# Shema.net
KiCad netlist of a schematic drawn in Altium Designer
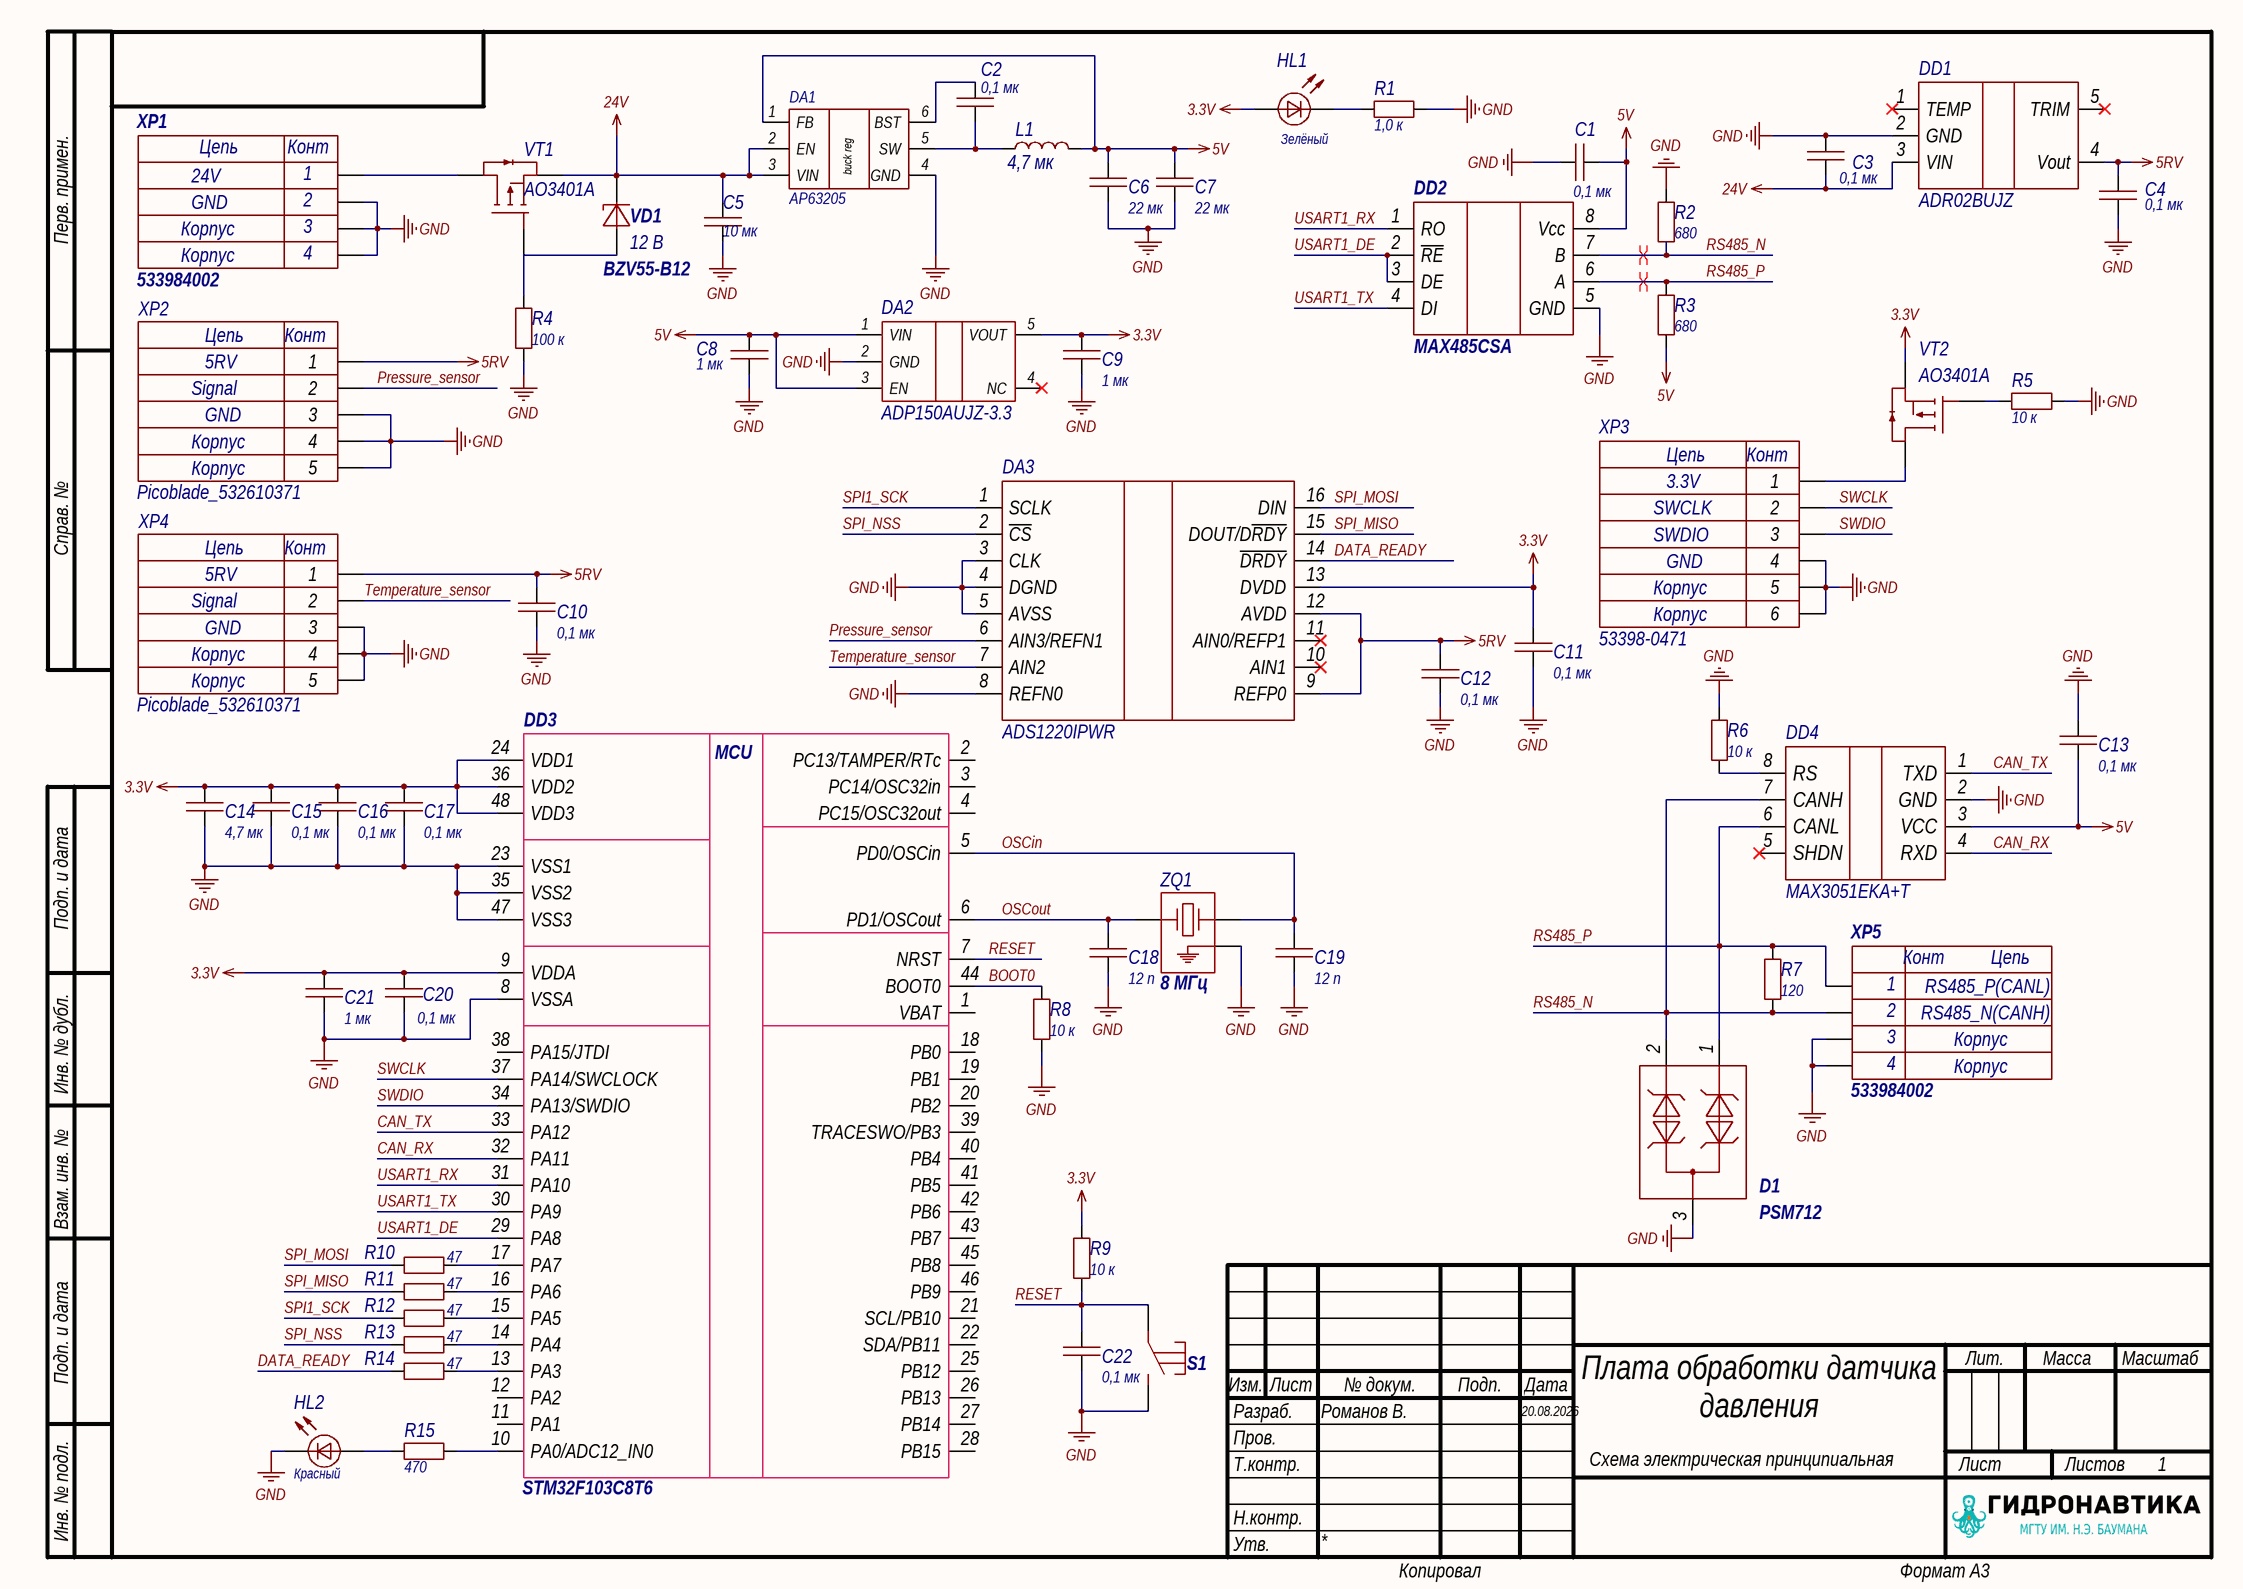
[diagram p0: Shema.SchDoc]

(export (version "E")
  (design (tool "Eeschema 10.0.6"))
  (components
    (comp (ref "C1")
      (value "0,1 мк")
      (footprint "0603C")
      (description "Конденсатор 0603C ёмкостью 0,1 мк 10%, 50 В, X7R")
      (fields (field (name "PART NUMBER") "Capacitor_0,1u_10_50V_X7R_0603C") (field (name "TOLERANCE") "10%"))
      (libsource (lib "Hydrolib") (part "Capacitor"))
    )
    (comp (ref "C2")
      (value "0,1 мк")
      (footprint "0603C")
      (description "Конденсатор 0603C ёмкостью 0,1 мк 10%, 50 В, X7R")
      (fields (field (name "PART NUMBER") "Capacitor_0,1u_10_50V_X7R_0603C") (field (name "TOLERANCE") "10%"))
      (libsource (lib "Hydrolib") (part "Capacitor"))
    )
    (comp (ref "C3")
      (value "0,1 мк")
      (footprint "0603C")
      (description "Конденсатор 0603C ёмкостью 0,1 мк 10%, 50 В, X7R")
      (fields (field (name "PART NUMBER") "Capacitor_0,1u_10_50V_X7R_0603C") (field (name "TOLERANCE") "10%"))
      (libsource (lib "Hydrolib") (part "Capacitor"))
    )
    (comp (ref "C4")
      (value "0,1 мк")
      (footprint "0603C")
      (description "Конденсатор 0603C ёмкостью 0,1 мк 10%, 50 В, X7R")
      (fields (field (name "PART NUMBER") "Capacitor_0,1u_10_50V_X7R_0603C") (field (name "TOLERANCE") "10%"))
      (libsource (lib "Hydrolib") (part "Capacitor"))
    )
    (comp (ref "C5")
      (value "10 мк")
      (footprint "1210C")
      (description "Конденсатор 1210C ёмкостью 10 мк 10%, 35 В, X7R")
      (fields (field (name "PART NUMBER") "Capacitor_10u_10_35V_X7R_1210C") (field (name "TOLERANCE") "10%"))
      (libsource (lib "Hydrolib") (part "Capacitor"))
    )
    (comp (ref "C6")
      (value "22 мк")
      (footprint "1210C")
      (description "Конденсатор 1210C ёмкостью 22 мк 10%, 25 В, X7R")
      (fields (field (name "PART NUMBER") "Capacitor_22u_10_25V_X7R_1210C") (field (name "TOLERANCE") "10%"))
      (libsource (lib "Hydrolib") (part "Capacitor"))
    )
    (comp (ref "C7")
      (value "22 мк")
      (footprint "1210C")
      (description "Конденсатор 1210C ёмкостью 22 мк 10%, 25 В, X7R")
      (fields (field (name "PART NUMBER") "Capacitor_22u_10_25V_X7R_1210C") (field (name "TOLERANCE") "10%"))
      (libsource (lib "Hydrolib") (part "Capacitor"))
    )
    (comp (ref "C8")
      (value "1 мк")
      (footprint "0603C")
      (description "Конденсатор 0603C ёмкостью 1 мк 10%, 25 В, X7R")
      (fields (field (name "PART NUMBER") "Capacitor_1u_10_25V_X7R_0603C") (field (name "TOLERANCE") "10%"))
      (libsource (lib "Hydrolib") (part "Capacitor"))
    )
    (comp (ref "C9")
      (value "1 мк")
      (footprint "0603C")
      (description "Конденсатор 0603C ёмкостью 1 мк 10%, 25 В, X7R")
      (fields (field (name "PART NUMBER") "Capacitor_1u_10_25V_X7R_0603C") (field (name "TOLERANCE") "10%"))
      (libsource (lib "Hydrolib") (part "Capacitor"))
    )
    (comp (ref "C10")
      (value "0,1 мк")
      (footprint "0603C")
      (description "Конденсатор 0603C ёмкостью 0,1 мк 10%, 50 В, X7R")
      (fields (field (name "PART NUMBER") "Capacitor_0,1u_10_50V_X7R_0603C") (field (name "TOLERANCE") "10%"))
      (libsource (lib "Hydrolib") (part "Capacitor"))
    )
    (comp (ref "C11")
      (value "0,1 мк")
      (footprint "0603C")
      (description "Конденсатор 0603C ёмкостью 0,1 мк 10%, 50 В, X7R")
      (fields (field (name "PART NUMBER") "Capacitor_0,1u_10_50V_X7R_0603C") (field (name "TOLERANCE") "10%"))
      (libsource (lib "Hydrolib") (part "Capacitor"))
    )
    (comp (ref "C12")
      (value "0,1 мк")
      (footprint "0603C")
      (description "Конденсатор 0603C ёмкостью 0,1 мк 10%, 50 В, X7R")
      (fields (field (name "PART NUMBER") "Capacitor_0,1u_10_50V_X7R_0603C") (field (name "TOLERANCE") "10%"))
      (libsource (lib "Hydrolib") (part "Capacitor"))
    )
    (comp (ref "C13")
      (value "0,1 мк")
      (footprint "0603C")
      (description "Конденсатор 0603C ёмкостью 0,1 мк 10%, 50 В, X7R")
      (fields (field (name "PART NUMBER") "Capacitor_0,1u_10_50V_X7R_0603C") (field (name "TOLERANCE") "10%"))
      (libsource (lib "Hydrolib") (part "Capacitor"))
    )
    (comp (ref "C14")
      (value "4,7 мк")
      (footprint "1206C")
      (description "Конденсатор 1206C ёмкостью 4,7 мк 10%, 50 В, X7R")
      (fields (field (name "PART NUMBER") "Capacitor_4,7u_10_50V_X7R_1206C") (field (name "TOLERANCE") "10%"))
      (libsource (lib "Hydrolib") (part "Capacitor"))
    )
    (comp (ref "C15")
      (value "0,1 мк")
      (footprint "0603C")
      (description "Конденсатор 0603C ёмкостью 0,1 мк 10%, 50 В, X7R")
      (fields (field (name "PART NUMBER") "Capacitor_0,1u_10_50V_X7R_0603C") (field (name "TOLERANCE") "10%"))
      (libsource (lib "Hydrolib") (part "Capacitor"))
    )
    (comp (ref "C16")
      (value "0,1 мк")
      (footprint "0603C")
      (description "Конденсатор 0603C ёмкостью 0,1 мк 10%, 50 В, X7R")
      (fields (field (name "PART NUMBER") "Capacitor_0,1u_10_50V_X7R_0603C") (field (name "TOLERANCE") "10%"))
      (libsource (lib "Hydrolib") (part "Capacitor"))
    )
    (comp (ref "C17")
      (value "0,1 мк")
      (footprint "0603C")
      (description "Конденсатор 0603C ёмкостью 0,1 мк 10%, 50 В, X7R")
      (fields (field (name "PART NUMBER") "Capacitor_0,1u_10_50V_X7R_0603C") (field (name "TOLERANCE") "10%"))
      (libsource (lib "Hydrolib") (part "Capacitor"))
    )
    (comp (ref "C18")
      (value "12 п")
      (footprint "0603C")
      (description "Конденсатор 0603C ёмкостью 12 п 5%, 50 В, NP0")
      (fields
        (field (name "PART NUMBER") "Capacitor_12p_5_50V_NP0_0603C")
        (field (name "TOLERANCE") "5%")
        (field (name "АВТОР") "glebmih")
      )
      (libsource (lib "Hydrolib") (part "Capacitor"))
    )
    (comp (ref "C19")
      (value "12 п")
      (footprint "0603C")
      (description "Конденсатор 0603C ёмкостью 12 п 5%, 50 В, NP0")
      (fields
        (field (name "PART NUMBER") "Capacitor_12p_5_50V_NP0_0603C")
        (field (name "TOLERANCE") "5%")
        (field (name "АВТОР") "glebmih")
      )
      (libsource (lib "Hydrolib") (part "Capacitor"))
    )
    (comp (ref "C20")
      (value "0,1 мк")
      (footprint "0603C")
      (description "Конденсатор 0603C ёмкостью 0,1 мк 10%, 50 В, X7R")
      (fields (field (name "PART NUMBER") "Capacitor_0,1u_10_50V_X7R_0603C") (field (name "TOLERANCE") "10%"))
      (libsource (lib "Hydrolib") (part "Capacitor"))
    )
    (comp (ref "C21")
      (value "1 мк")
      (footprint "0603C")
      (description "Конденсатор 0603C ёмкостью 1 мк 10%, 25 В, X7R")
      (fields (field (name "PART NUMBER") "Capacitor_1u_10_25V_X7R_0603C") (field (name "TOLERANCE") "10%"))
      (libsource (lib "Hydrolib") (part "Capacitor"))
    )
    (comp (ref "C22")
      (value "0,1 мк")
      (footprint "0603C")
      (description "Конденсатор 0603C ёмкостью 0,1 мк 10%, 50 В, X7R")
      (fields (field (name "PART NUMBER") "Capacitor_0,1u_10_50V_X7R_0603C") (field (name "TOLERANCE") "10%"))
      (libsource (lib "Hydrolib") (part "Capacitor"))
    )
    (comp (ref "D1")
      (value "PSM712")
      (footprint "SOT23-3")
      (description "Защитный диод для линии RS-485")
      (libsource (lib "Hydrolib") (part "TVS_2_2dir"))
    )
    (comp (ref "DA1")
      (value "AP63205")
      (footprint "TSOT26")
      (description "DC-DC понижающий преобразователь, Vin: 3.8 - 40 В; 5 В; 2 А")
      (fields (field (name "АВТОР") "glebmih"))
      (libsource (lib "Hydrolib") (part "AP63205"))
    )
    (comp (ref "DA2")
      (value "ADP150AUJZ-3.3")
      (footprint "SOT23-5")
      (description "Стабилизатор напряжения 3.3В 150мА")
      (fields (field (name "АВТОР") "glebmih"))
      (libsource (lib "Hydrolib") (part "ADP150AUJZ-3.3"))
    )
    (comp (ref "DA3")
      (value "ADS1220IPWR")
      (footprint "TSSOP-16")
      (description "24-Бит Sigma-Delta аналого-цифровой преобразователь")
      (fields (field (name "АВТОР") "Vouka06"))
      (libsource (lib "Hydrolib") (part "ADS1220IPWR"))
    )
    (comp (ref "DD1")
      (value "ADR02BUJZ")
      (footprint "SOT23-5")
      (description "Источник опорного напряжения, 5В")
      (fields (field (name "АВТОР") "Vouka05"))
      (libsource (lib "Hydrolib") (part "ADR02BUJZ"))
    )
    (comp (ref "DD2")
      (value "MAX485CSA")
      (footprint "SOIC-8")
      (description "RS-485 приёмопередатчик")
      (libsource (lib "Hydrolib") (part "MAX485CSA"))
    )
    (comp (ref "DD3")
      (value "STM32F103C8T6")
      (footprint "LQFP48")
      (description "Микроконтроллер")
      (fields (field (name "MANUFACTURER") "ST Microelectronics") (field (name "VALUE1") "MCU"))
      (libsource (lib "Hydrolib") (part "STM32F103C8T6"))
    )
    (comp (ref "DD4")
      (value "MAX3051EKA+T")
      (footprint "SOT-23-8")
      (description "CAN трансивер 1Mbps +3.3В")
      (fields (field (name "АВТОР") "Vouka06"))
      (libsource (lib "Hydrolib") (part "MAX3051EKA+T"))
    )
    (comp (ref "HL1")
      (value "Зелёный")
      (footprint "0805D")
      (description "Светодиод")
      (fields (field (name "PART NUMBER") "LED"))
      (libsource (lib "Hydrolib") (part "LED"))
    )
    (comp (ref "HL2")
      (value "Красный")
      (footprint "0805D")
      (description "Светодиод")
      (fields (field (name "PART NUMBER") "LED"))
      (libsource (lib "Hydrolib") (part "LED"))
    )
    (comp (ref "L1")
      (value "4,7 мк")
      (footprint "IHLP-2525")
      (description "ЧИП-индуктивность экранированная 4,7мкГн ±20% 5,5A 40мОм 2525")
      (fields (field (name "PART NUMBER") "IHLP2525CZER4R7M01"))
      (libsource (lib "Hydrolib") (part "Inductance"))
    )
    (comp (ref "R1")
      (value "1,0 к")
      (footprint "0603R")
      (description "Резистор номиналом 1,0 кОм 1%")
      (fields (field (name "PART NUMBER") "Resistor_1.0k_1_0603") (field (name "TOLERANCE") "1%"))
      (libsource (lib "") (part "Resistor_2"))
    )
    (comp (ref "R2")
      (value "680")
      (footprint "0603R")
      (description "Резистор номиналом 680 Ом 1%")
      (fields (field (name "PART NUMBER") "Resistor_680_1_0603") (field (name "TOLERANCE") "1%"))
      (libsource (lib "") (part "Resistor_1"))
    )
    (comp (ref "R3")
      (value "680")
      (footprint "0603R")
      (description "Резистор номиналом 680 Ом 1%")
      (fields (field (name "PART NUMBER") "Resistor_680_1_0603") (field (name "TOLERANCE") "1%"))
      (libsource (lib "") (part "Resistor_1"))
    )
    (comp (ref "R4")
      (value "100 к")
      (footprint "0603R")
      (description "Резистор номиналом 100 кОм 1%")
      (fields (field (name "PART NUMBER") "Resistor_100k_1_0603") (field (name "TOLERANCE") "1%"))
      (libsource (lib "") (part "Resistor_1"))
    )
    (comp (ref "R5")
      (value "10 к")
      (footprint "0603R")
      (description "Резистор номиналом 10 кОм 1%")
      (fields (field (name "PART NUMBER") "Resistor_10k_1_0603") (field (name "TOLERANCE") "1%"))
      (libsource (lib "") (part "Resistor_2"))
    )
    (comp (ref "R6")
      (value "10 к")
      (footprint "0603R")
      (description "Резистор номиналом 10 кОм 1%")
      (fields (field (name "PART NUMBER") "Resistor_10k_1_0603") (field (name "TOLERANCE") "1%"))
      (libsource (lib "") (part "Resistor_2"))
    )
    (comp (ref "R7")
      (value "120")
      (footprint "0603R")
      (description "Резистор номиналом 120 Ом 1%")
      (fields (field (name "PART NUMBER") "Resistor_120_1_0603") (field (name "TOLERANCE") "1%"))
      (libsource (lib "") (part "Resistor_1"))
    )
    (comp (ref "R8")
      (value "10 к")
      (footprint "0603R")
      (description "Резистор номиналом 10 кОм 1%")
      (fields (field (name "PART NUMBER") "Resistor_10k_1_0603") (field (name "TOLERANCE") "1%"))
      (libsource (lib "Hydrolib") (part "Resistor"))
    )
    (comp (ref "R9")
      (value "10 к")
      (footprint "0603R")
      (description "Резистор номиналом 10 кОм 1%")
      (fields (field (name "PART NUMBER") "Resistor_10k_1_0603") (field (name "TOLERANCE") "1%"))
      (libsource (lib "Hydrolib") (part "Resistor"))
    )
    (comp (ref "R10")
      (value "47")
      (footprint "0603R")
      (description "Резистор номиналом 47 Ом 1%")
      (fields (field (name "PART NUMBER") "Resistor_47_1_0603") (field (name "TOLERANCE") "1%"))
      (libsource (lib "") (part "Resistor_2"))
    )
    (comp (ref "R11")
      (value "47")
      (footprint "0603R")
      (description "Резистор номиналом 47 Ом 1%")
      (fields (field (name "PART NUMBER") "Resistor_47_1_0603") (field (name "TOLERANCE") "1%"))
      (libsource (lib "") (part "Resistor_2"))
    )
    (comp (ref "R12")
      (value "47")
      (footprint "0603R")
      (description "Резистор номиналом 47 Ом 1%")
      (fields (field (name "PART NUMBER") "Resistor_47_1_0603") (field (name "TOLERANCE") "1%"))
      (libsource (lib "") (part "Resistor_2"))
    )
    (comp (ref "R13")
      (value "47")
      (footprint "0603R")
      (description "Резистор номиналом 47 Ом 1%")
      (fields (field (name "PART NUMBER") "Resistor_47_1_0603") (field (name "TOLERANCE") "1%"))
      (libsource (lib "") (part "Resistor_2"))
    )
    (comp (ref "R14")
      (value "47")
      (footprint "0603R")
      (description "Резистор номиналом 47 Ом 1%")
      (fields (field (name "PART NUMBER") "Resistor_47_1_0603") (field (name "TOLERANCE") "1%"))
      (libsource (lib "") (part "Resistor_2"))
    )
    (comp (ref "R15")
      (value "470")
      (footprint "0603R")
      (description "Резистор номиналом 470 Ом 1%")
      (fields (field (name "PART NUMBER") "Resistor_470_1_0603") (field (name "TOLERANCE") "1%"))
      (libsource (lib "") (part "Resistor_2"))
    )
    (comp (ref "S1")
      (value "Tact_button")
      (footprint "Button_SMD_10mm")
      (description "Тактовая кнопка")
      (libsource (lib "Hydrolib") (part "Tact_button"))
    )
    (comp (ref "VD1")
      (value "BZV55-B12")
      (footprint "mini_MELF_3.5mm")
      (description "Стабилитрон 12В, 5%, 0.5Вт")
      (fields (field (name "ALTIUM_VALUE") "12 В") (field (name "АВТОР") "rreali"))
      (libsource (lib "Hydrolib") (part "Zener"))
    )
    (comp (ref "VT1")
      (value "AO3401A")
      (footprint "SOT23-3")
      (description "P-канальный MOSFET")
      (libsource (lib "Hydrolib") (part "MOSFET P-channel 2"))
    )
    (comp (ref "VT2")
      (value "AO3401A")
      (footprint "SOT23-3")
      (description "P-канальный MOSFET")
      (libsource (lib "Hydrolib") (part "MOSFET P-channel 2"))
    )
    (comp (ref "XP1")
      (value "533984002")
      (footprint "Picoblade_533984002")
      (description "2pin, 1.25mm, вилка, PicoBlade, на плату, SMT")
      (fields
        (field (name "VALUE3") "Корпус")
        (field (name "VALUE2") "GND")
        (field (name "VALUE4") "Корпус")
        (field (name "VALUE1") "24V")
        (field (name "PART NUMBER") "Picoblade_533984002")
        (field (name "АВТОР") "rreali")
      )
      (libsource (lib "Hydrolib") (part "Conn_2pin_2shield"))
    )
    (comp (ref "XP2")
      (value "Picoblade_532610371")
      (footprint "CONN_532610001-SD_03_MOL")
      (description "Picoblade 3-pin разъем")
      (fields
        (field (name "VALUE5") "Корпус")
        (field (name "VALUE4") "Корпус")
        (field (name "VALUE3") "GND")
        (field (name "VALUE2") "Signal")
        (field (name "VALUE1") "5RV")
        (field (name "АВТОР") "Vouka06")
      )
      (libsource (lib "Hydrolib") (part "Picoblade_532610371"))
    )
    (comp (ref "XP3")
      (value "53398-0471")
      (footprint "53398-0471")
      (description "Разъем PicoBlade 1.25 мм, 4pin")
      (fields
        (field (name "VALUE6") "Корпус")
        (field (name "VALUE5") "Корпус")
        (field (name "VALUE4") "GND")
        (field (name "VALUE3") "SWDIO")
        (field (name "VALUE2") "SWCLK")
        (field (name "VALUE1") "3.3V")
        (field (name "PART NUMBER") "PicoBlade_53398-0471")
        (field (name "АВТОР") "Vouka06")
      )
      (libsource (lib "Hydrolib") (part "PicoBlade_53398-0471"))
    )
    (comp (ref "XP4")
      (value "Picoblade_532610371")
      (footprint "CONN_532610001-SD_03_MOL")
      (description "Picoblade 3-pin разъем")
      (fields
        (field (name "VALUE5") "Корпус")
        (field (name "VALUE4") "Корпус")
        (field (name "VALUE3") "GND")
        (field (name "VALUE2") "Signal")
        (field (name "VALUE1") "5RV")
        (field (name "АВТОР") "Vouka06")
      )
      (libsource (lib "Hydrolib") (part "Picoblade_532610371"))
    )
    (comp (ref "XP5")
      (value "533984002")
      (footprint "Picoblade_533984002")
      (description "2pin, 1.25mm, вилка, PicoBlade, на плату, SMT")
      (fields
        (field (name "VALUE3") "Корпус")
        (field (name "VALUE2") "RS485_N(CANH)")
        (field (name "VALUE4") "Корпус")
        (field (name "VALUE1") "RS485_P(CANL)")
        (field (name "PART NUMBER") "Picoblade_533984002")
        (field (name "АВТОР") "rreali")
      )
      (libsource (lib "Hydrolib") (part "Conn_2pin_2shield"))
    )
    (comp (ref "ZQ1")
      (value "8 МГц")
      (footprint "QSMD3.2x2.5")
      (description "Кварцевый резонатор с входом земли")
      (fields (field (name "PART NUMBER") "XTAL_GND"))
      (libsource (lib "Hydrolib") (part "XTAL_GND"))
    )
  )
  (nets
    (net (code "1") (name "/BOOT0") (class "Default")
      (node (ref "DD3") (pin "44") (pinfunction "BOOT0_44") (pintype "passive"))
      (node (ref "R8") (pin "1") (pinfunction "1_1") (pintype "passive"))
    )
    (net (code "2") (name "/CAN_RX") (class "Default")
      (node (ref "DD3") (pin "32") (pinfunction "PA11_32") (pintype "passive"))
      (node (ref "DD4") (pin "4") (pinfunction "RXD_4") (pintype "passive"))
    )
    (net (code "3") (name "/CAN_TX") (class "Default")
      (node (ref "DD3") (pin "33") (pinfunction "PA12_33") (pintype "passive"))
      (node (ref "DD4") (pin "1") (pinfunction "TXD_1") (pintype "passive"))
    )
    (net (code "4") (name "/DATA_READY") (class "Default")
      (node (ref "DA3") (pin "14") (pinfunction "~{DRDY}_14") (pintype "passive"))
      (node (ref "R14") (pin "1") (pinfunction "1_1") (pintype "passive"))
    )
    (net (code "5") (name "/OSCin") (class "Default")
      (node (ref "C19") (pin "2") (pinfunction "2_2") (pintype "passive"))
      (node (ref "DD3") (pin "5") (pinfunction "PD0/OSCin_5") (pintype "passive"))
      (node (ref "ZQ1") (pin "2") (pinfunction "2_2") (pintype "passive"))
    )
    (net (code "6") (name "/OSCout") (class "Default")
      (node (ref "C18") (pin "2") (pinfunction "2_2") (pintype "passive"))
      (node (ref "DD3") (pin "6") (pinfunction "PD1/OSCout_6") (pintype "passive"))
      (node (ref "ZQ1") (pin "1") (pinfunction "1_1") (pintype "passive"))
    )
    (net (code "7") (name "/Pressure_sensor") (class "Default")
      (node (ref "DA3") (pin "6") (pinfunction "AIN3/REFN1_6") (pintype "passive"))
      (node (ref "XP2") (pin "2") (pinfunction "2_2") (pintype "passive"))
    )
    (net (code "8") (name "/RESET") (class "Default")
      (node (ref "C22") (pin "1") (pinfunction "1_1") (pintype "passive"))
      (node (ref "DD3") (pin "7") (pinfunction "NRST_7") (pintype "passive"))
      (node (ref "R9") (pin "2") (pinfunction "2_2") (pintype "passive"))
      (node (ref "S1") (pin "1") (pinfunction "1_1") (pintype "passive"))
    )
    (net (code "9") (name "/RS485_N") (class "Default")
      (node (ref "D1") (pin "2") (pinfunction "15_2") (pintype "passive"))
      (node (ref "DD2") (pin "7") (pinfunction "B_7") (pintype "passive"))
      (node (ref "DD4") (pin "7") (pinfunction "CANH_7") (pintype "passive"))
      (node (ref "R2") (pin "1") (pinfunction "1_1") (pintype "passive"))
      (node (ref "R7") (pin "1") (pinfunction "1_1") (pintype "passive"))
      (node (ref "XP5") (pin "2") (pinfunction "2_2") (pintype "passive"))
    )
    (net (code "10") (name "/RS485_P") (class "Default")
      (node (ref "D1") (pin "1") (pinfunction "14_1") (pintype "passive"))
      (node (ref "DD2") (pin "6") (pinfunction "A_6") (pintype "passive"))
      (node (ref "DD4") (pin "6") (pinfunction "CANL_6") (pintype "passive"))
      (node (ref "R3") (pin "2") (pinfunction "2_2") (pintype "passive"))
      (node (ref "R7") (pin "2") (pinfunction "2_2") (pintype "passive"))
      (node (ref "XP5") (pin "1") (pinfunction "1_1") (pintype "passive"))
    )
    (net (code "11") (name "/SPI1_SCK") (class "Default")
      (node (ref "DA3") (pin "1") (pinfunction "SCLK_1") (pintype "passive"))
      (node (ref "R12") (pin "1") (pinfunction "1_1") (pintype "passive"))
    )
    (net (code "12") (name "/SPI_MISO") (class "Default")
      (node (ref "DA3") (pin "15") (pinfunction "DOUT/D~{RDY}_15") (pintype "passive"))
      (node (ref "R11") (pin "1") (pinfunction "1_1") (pintype "passive"))
    )
    (net (code "13") (name "/SPI_MOSI") (class "Default")
      (node (ref "DA3") (pin "16") (pinfunction "DIN_16") (pintype "passive"))
      (node (ref "R10") (pin "1") (pinfunction "1_1") (pintype "passive"))
    )
    (net (code "14") (name "/SPI_NSS") (class "Default")
      (node (ref "DA3") (pin "2") (pinfunction "~{CS}_2") (pintype "passive"))
      (node (ref "R13") (pin "1") (pinfunction "1_1") (pintype "passive"))
    )
    (net (code "15") (name "/SWCLK") (class "Default")
      (node (ref "DD3") (pin "37") (pinfunction "PA14/SWCLOCK_37") (pintype "passive"))
      (node (ref "XP3") (pin "2") (pinfunction "2_2") (pintype "passive"))
    )
    (net (code "16") (name "/SWDIO") (class "Default")
      (node (ref "DD3") (pin "34") (pinfunction "PA13/SWDIO_34") (pintype "passive"))
      (node (ref "XP3") (pin "3") (pinfunction "3_3") (pintype "passive"))
    )
    (net (code "17") (name "/Temperature_sensor") (class "Default")
      (node (ref "DA3") (pin "7") (pinfunction "AIN2_7") (pintype "passive"))
      (node (ref "XP4") (pin "2") (pinfunction "2_2") (pintype "passive"))
    )
    (net (code "18") (name "/USART1_DE") (class "Default")
      (node (ref "DD2") (pin "2") (pinfunction "RE_2") (pintype "passive"))
      (node (ref "DD2") (pin "3") (pinfunction "DE_3") (pintype "passive"))
      (node (ref "DD3") (pin "29") (pinfunction "PA8_29") (pintype "passive"))
    )
    (net (code "19") (name "/USART1_RX") (class "Default")
      (node (ref "DD2") (pin "1") (pinfunction "RO_1") (pintype "passive"))
      (node (ref "DD3") (pin "31") (pinfunction "PA10_31") (pintype "passive"))
    )
    (net (code "20") (name "/USART1_TX") (class "Default")
      (node (ref "DD2") (pin "4") (pinfunction "DI_4") (pintype "passive"))
      (node (ref "DD3") (pin "30") (pinfunction "PA9_30") (pintype "passive"))
    )
    (net (code "21") (name "3.3V") (class "Default")
      (node (ref "C11") (pin "2") (pinfunction "2_2") (pintype "passive"))
      (node (ref "C14") (pin "2") (pinfunction "2_2") (pintype "passive"))
      (node (ref "C15") (pin "2") (pinfunction "2_2") (pintype "passive"))
      (node (ref "C16") (pin "2") (pinfunction "2_2") (pintype "passive"))
      (node (ref "C17") (pin "2") (pinfunction "2_2") (pintype "passive"))
      (node (ref "C20") (pin "2") (pinfunction "2_2") (pintype "passive"))
      (node (ref "C21") (pin "2") (pinfunction "2_2") (pintype "passive"))
      (node (ref "C9") (pin "2") (pinfunction "2_2") (pintype "passive"))
      (node (ref "DA2") (pin "5") (pinfunction "VOUT_5") (pintype "passive"))
      (node (ref "DA3") (pin "13") (pinfunction "DVDD_13") (pintype "passive"))
      (node (ref "DD3") (pin "24") (pinfunction "VDD1_24") (pintype "passive"))
      (node (ref "DD3") (pin "36") (pinfunction "VDD2_36") (pintype "passive"))
      (node (ref "DD3") (pin "48") (pinfunction "VDD3_48") (pintype "passive"))
      (node (ref "DD3") (pin "9") (pinfunction "VDDA_9") (pintype "passive"))
      (node (ref "HL1") (pin "1") (pinfunction "1_1") (pintype "passive"))
      (node (ref "R9") (pin "1") (pinfunction "1_1") (pintype "passive"))
      (node (ref "VT2") (pin "2") (pinfunction "2_2") (pintype "passive"))
    )
    (net (code "22") (name "5RV") (class "Default")
      (node (ref "C10") (pin "2") (pinfunction "2_2") (pintype "passive"))
      (node (ref "C12") (pin "2") (pinfunction "2_2") (pintype "passive"))
      (node (ref "C4") (pin "2") (pinfunction "2_2") (pintype "passive"))
      (node (ref "DA3") (pin "12") (pinfunction "AVDD_12") (pintype "passive"))
      (node (ref "DA3") (pin "9") (pinfunction "REFP0_9") (pintype "passive"))
      (node (ref "DD1") (pin "4") (pinfunction "Vout_4") (pintype "passive"))
      (node (ref "XP2") (pin "1") (pinfunction "1_1") (pintype "passive"))
      (node (ref "XP4") (pin "1") (pinfunction "1_1") (pintype "passive"))
    )
    (net (code "23") (name "5V") (class "Default")
      (node (ref "C1") (pin "2") (pinfunction "2_2") (pintype "passive"))
      (node (ref "C13") (pin "2") (pinfunction "2_2") (pintype "passive"))
      (node (ref "C6") (pin "2") (pinfunction "2_2") (pintype "passive"))
      (node (ref "C7") (pin "2") (pinfunction "2_2") (pintype "passive"))
      (node (ref "C8") (pin "2") (pinfunction "2_2") (pintype "passive"))
      (node (ref "DA1") (pin "1") (pinfunction "FB_1") (pintype "passive"))
      (node (ref "DA2") (pin "1") (pinfunction "VIN_1") (pintype "passive"))
      (node (ref "DA2") (pin "3") (pinfunction "EN_3") (pintype "passive"))
      (node (ref "DD2") (pin "8") (pinfunction "Vcc_8") (pintype "passive"))
      (node (ref "DD4") (pin "3") (pinfunction "VCC_3") (pintype "passive"))
      (node (ref "L1") (pin "2") (pinfunction "2_2") (pintype "passive"))
      (node (ref "R3") (pin "1") (pinfunction "1_1") (pintype "passive"))
    )
    (net (code "24") (name "24V") (class "Default")
      (node (ref "C3") (pin "1") (pinfunction "1_1") (pintype "passive"))
      (node (ref "C5") (pin "2") (pinfunction "2_2") (pintype "passive"))
      (node (ref "DA1") (pin "2") (pinfunction "EN_2") (pintype "passive"))
      (node (ref "DA1") (pin "3") (pinfunction "VIN_3") (pintype "passive"))
      (node (ref "DD1") (pin "3") (pinfunction "VIN_3") (pintype "passive"))
      (node (ref "VD1") (pin "2") (pinfunction "2_2") (pintype "passive"))
      (node (ref "VT1") (pin "2") (pinfunction "2_2") (pintype "passive"))
    )
    (net (code "25") (name "GND") (class "Default")
      (node (ref "C1") (pin "1") (pinfunction "1_1") (pintype "passive"))
      (node (ref "C10") (pin "1") (pinfunction "1_1") (pintype "passive"))
      (node (ref "C11") (pin "1") (pinfunction "1_1") (pintype "passive"))
      (node (ref "C12") (pin "1") (pinfunction "1_1") (pintype "passive"))
      (node (ref "C13") (pin "1") (pinfunction "1_1") (pintype "passive"))
      (node (ref "C14") (pin "1") (pinfunction "1_1") (pintype "passive"))
      (node (ref "C15") (pin "1") (pinfunction "1_1") (pintype "passive"))
      (node (ref "C16") (pin "1") (pinfunction "1_1") (pintype "passive"))
      (node (ref "C17") (pin "1") (pinfunction "1_1") (pintype "passive"))
      (node (ref "C18") (pin "1") (pinfunction "1_1") (pintype "passive"))
      (node (ref "C19") (pin "1") (pinfunction "1_1") (pintype "passive"))
      (node (ref "C20") (pin "1") (pinfunction "1_1") (pintype "passive"))
      (node (ref "C21") (pin "1") (pinfunction "1_1") (pintype "passive"))
      (node (ref "C22") (pin "2") (pinfunction "2_2") (pintype "passive"))
      (node (ref "C3") (pin "2") (pinfunction "2_2") (pintype "passive"))
      (node (ref "C4") (pin "1") (pinfunction "1_1") (pintype "passive"))
      (node (ref "C5") (pin "1") (pinfunction "1_1") (pintype "passive"))
      (node (ref "C6") (pin "1") (pinfunction "1_1") (pintype "passive"))
      (node (ref "C7") (pin "1") (pinfunction "1_1") (pintype "passive"))
      (node (ref "C8") (pin "1") (pinfunction "1_1") (pintype "passive"))
      (node (ref "C9") (pin "1") (pinfunction "1_1") (pintype "passive"))
      (node (ref "D1") (pin "3") (pinfunction "16_3") (pintype "passive"))
      (node (ref "DA1") (pin "4") (pinfunction "GND_4") (pintype "passive"))
      (node (ref "DA2") (pin "2") (pinfunction "GND_2") (pintype "passive"))
      (node (ref "DA3") (pin "3") (pinfunction "CLK_3") (pintype "passive"))
      (node (ref "DA3") (pin "4") (pinfunction "DGND_4") (pintype "passive"))
      (node (ref "DA3") (pin "5") (pinfunction "AVSS_5") (pintype "passive"))
      (node (ref "DA3") (pin "8") (pinfunction "REFN0_8") (pintype "passive"))
      (node (ref "DD1") (pin "2") (pinfunction "GND_2") (pintype "passive"))
      (node (ref "DD2") (pin "5") (pinfunction "GND_5") (pintype "passive"))
      (node (ref "DD3") (pin "23") (pinfunction "VSS1_23") (pintype "passive"))
      (node (ref "DD3") (pin "35") (pinfunction "VSS2_35") (pintype "passive"))
      (node (ref "DD3") (pin "47") (pinfunction "VSS3_47") (pintype "passive"))
      (node (ref "DD3") (pin "8") (pinfunction "VSSA_8") (pintype "passive"))
      (node (ref "DD4") (pin "2") (pinfunction "GND_2") (pintype "passive"))
      (node (ref "HL2") (pin "2") (pinfunction "2_2") (pintype "passive"))
      (node (ref "R1") (pin "2") (pinfunction "2_2") (pintype "passive"))
      (node (ref "R2") (pin "2") (pinfunction "2_2") (pintype "passive"))
      (node (ref "R4") (pin "1") (pinfunction "1_1") (pintype "passive"))
      (node (ref "R5") (pin "2") (pinfunction "2_2") (pintype "passive"))
      (node (ref "R6") (pin "2") (pinfunction "2_2") (pintype "passive"))
      (node (ref "R8") (pin "2") (pinfunction "2_2") (pintype "passive"))
      (node (ref "S1") (pin "2") (pinfunction "2_2") (pintype "passive"))
      (node (ref "XP1") (pin "2") (pinfunction "2_2") (pintype "passive"))
      (node (ref "XP1") (pin "3") (pinfunction "3_3") (pintype "passive"))
      (node (ref "XP1") (pin "4") (pinfunction "4_4") (pintype "passive"))
      (node (ref "XP2") (pin "3") (pinfunction "3_3") (pintype "passive"))
      (node (ref "XP2") (pin "4") (pinfunction "4_4") (pintype "passive"))
      (node (ref "XP2") (pin "5") (pinfunction "5_5") (pintype "passive"))
      (node (ref "XP3") (pin "4") (pinfunction "4_4") (pintype "passive"))
      (node (ref "XP3") (pin "5") (pinfunction "5_5") (pintype "passive"))
      (node (ref "XP3") (pin "6") (pinfunction "6_6") (pintype "passive"))
      (node (ref "XP4") (pin "3") (pinfunction "3_3") (pintype "passive"))
      (node (ref "XP4") (pin "4") (pinfunction "4_4") (pintype "passive"))
      (node (ref "XP4") (pin "5") (pinfunction "5_5") (pintype "passive"))
      (node (ref "XP5") (pin "3") (pinfunction "3_3") (pintype "passive"))
      (node (ref "XP5") (pin "4") (pinfunction "4_4") (pintype "passive"))
      (node (ref "ZQ1") (pin "3") (pinfunction "3_3") (pintype "passive"))
    )
    (net (code "26") (name "Net-(DA1-BST)") (class "Default")
      (node (ref "C2") (pin "2") (pinfunction "2_2") (pintype "passive"))
      (node (ref "DA1") (pin "6") (pinfunction "BST_6") (pintype "passive"))
    )
    (net (code "27") (name "Net-(DA1-SW)") (class "Default")
      (node (ref "C2") (pin "1") (pinfunction "1_1") (pintype "passive"))
      (node (ref "DA1") (pin "5") (pinfunction "SW_5") (pintype "passive"))
      (node (ref "L1") (pin "1") (pinfunction "1_1") (pintype "passive"))
    )
    (net (code "28") (name "Net-(DD3-PA0{slash}ADC12_IN0)") (class "Default")
      (node (ref "DD3") (pin "10") (pinfunction "PA0/ADC12_IN0_10") (pintype "passive"))
      (node (ref "R15") (pin "2") (pinfunction "2_2") (pintype "passive"))
    )
    (net (code "29") (name "Net-(DD3-PA3)") (class "Default")
      (node (ref "DD3") (pin "13") (pinfunction "PA3_13") (pintype "passive"))
      (node (ref "R14") (pin "2") (pinfunction "2_2") (pintype "passive"))
    )
    (net (code "30") (name "Net-(DD3-PA4)") (class "Default")
      (node (ref "DD3") (pin "14") (pinfunction "PA4_14") (pintype "passive"))
      (node (ref "R13") (pin "2") (pinfunction "2_2") (pintype "passive"))
    )
    (net (code "31") (name "Net-(DD3-PA5)") (class "Default")
      (node (ref "DD3") (pin "15") (pinfunction "PA5_15") (pintype "passive"))
      (node (ref "R12") (pin "2") (pinfunction "2_2") (pintype "passive"))
    )
    (net (code "32") (name "Net-(DD3-PA6)") (class "Default")
      (node (ref "DD3") (pin "16") (pinfunction "PA6_16") (pintype "passive"))
      (node (ref "R11") (pin "2") (pinfunction "2_2") (pintype "passive"))
    )
    (net (code "33") (name "Net-(DD3-PA7)") (class "Default")
      (node (ref "DD3") (pin "17") (pinfunction "PA7_17") (pintype "passive"))
      (node (ref "R10") (pin "2") (pinfunction "2_2") (pintype "passive"))
    )
    (net (code "34") (name "Net-(DD4-RS)") (class "Default")
      (node (ref "DD4") (pin "8") (pinfunction "RS_8") (pintype "passive"))
      (node (ref "R6") (pin "1") (pinfunction "1_1") (pintype "passive"))
    )
    (net (code "35") (name "Net-(HL1-Pad2)") (class "Default")
      (node (ref "HL1") (pin "2") (pinfunction "2_2") (pintype "passive"))
      (node (ref "R1") (pin "1") (pinfunction "1_1") (pintype "passive"))
    )
    (net (code "36") (name "Net-(HL2-Pad1)") (class "Default")
      (node (ref "HL2") (pin "1") (pinfunction "1_1") (pintype "passive"))
      (node (ref "R15") (pin "1") (pinfunction "1_1") (pintype "passive"))
    )
    (net (code "37") (name "Net-(R4-Pad2)") (class "Default")
      (node (ref "R4") (pin "2") (pinfunction "2_2") (pintype "passive"))
      (node (ref "VD1") (pin "1") (pinfunction "1_1") (pintype "passive"))
      (node (ref "VT1") (pin "1") (pinfunction "1_1") (pintype "passive"))
    )
    (net (code "38") (name "Net-(R5-Pad1)") (class "Default")
      (node (ref "R5") (pin "1") (pinfunction "1_1") (pintype "passive"))
      (node (ref "VT2") (pin "1") (pinfunction "1_1") (pintype "passive"))
    )
    (net (code "39") (name "Net-(VT1-Pad3)") (class "Default")
      (node (ref "VT1") (pin "3") (pinfunction "3_3") (pintype "passive"))
      (node (ref "XP1") (pin "1") (pinfunction "1_1") (pintype "passive"))
    )
    (net (code "40") (name "Net-(VT2-Pad3)") (class "Default")
      (node (ref "VT2") (pin "3") (pinfunction "3_3") (pintype "passive"))
      (node (ref "XP3") (pin "1") (pinfunction "1_1") (pintype "passive"))
    )
    (net (code "41") (name "unconnected-(DA2-NC-Pad4)") (class "Default")
      (node (ref "DA2") (pin "4") (pinfunction "NC_4") (pintype "passive+no_connect"))
    )
    (net (code "42") (name "unconnected-(DA3-AIN0{slash}REFP1-Pad11)") (class "Default")
      (node (ref "DA3") (pin "11") (pinfunction "AIN0/REFP1_11") (pintype "passive+no_connect"))
    )
    (net (code "43") (name "unconnected-(DA3-AIN1-Pad10)") (class "Default")
      (node (ref "DA3") (pin "10") (pinfunction "AIN1_10") (pintype "passive+no_connect"))
    )
    (net (code "44") (name "unconnected-(DD1-TEMP-Pad1)") (class "Default")
      (node (ref "DD1") (pin "1") (pinfunction "TEMP_1") (pintype "passive+no_connect"))
    )
    (net (code "45") (name "unconnected-(DD1-TRIM-Pad5)") (class "Default")
      (node (ref "DD1") (pin "5") (pinfunction "TRIM_5") (pintype "passive+no_connect"))
    )
    (net (code "46") (name "unconnected-(DD3-PA1-Pad11)") (class "Default")
      (node (ref "DD3") (pin "11") (pinfunction "PA1_11") (pintype "passive"))
    )
    (net (code "47") (name "unconnected-(DD3-PA2-Pad12)") (class "Default")
      (node (ref "DD3") (pin "12") (pinfunction "PA2_12") (pintype "passive"))
    )
    (net (code "48") (name "unconnected-(DD3-PA15{slash}JTDI-Pad38)") (class "Default")
      (node (ref "DD3") (pin "38") (pinfunction "PA15/JTDI_38") (pintype "passive"))
    )
    (net (code "49") (name "unconnected-(DD3-PB0-Pad18)") (class "Default")
      (node (ref "DD3") (pin "18") (pinfunction "PB0_18") (pintype "passive"))
    )
    (net (code "50") (name "unconnected-(DD3-PB1-Pad19)") (class "Default")
      (node (ref "DD3") (pin "19") (pinfunction "PB1_19") (pintype "passive"))
    )
    (net (code "51") (name "unconnected-(DD3-PB2-Pad20)") (class "Default")
      (node (ref "DD3") (pin "20") (pinfunction "PB2_20") (pintype "passive"))
    )
    (net (code "52") (name "unconnected-(DD3-PB4-Pad40)") (class "Default")
      (node (ref "DD3") (pin "40") (pinfunction "PB4_40") (pintype "passive"))
    )
    (net (code "53") (name "unconnected-(DD3-PB5-Pad41)") (class "Default")
      (node (ref "DD3") (pin "41") (pinfunction "PB5_41") (pintype "passive"))
    )
    (net (code "54") (name "unconnected-(DD3-PB6-Pad42)") (class "Default")
      (node (ref "DD3") (pin "42") (pinfunction "PB6_42") (pintype "passive"))
    )
    (net (code "55") (name "unconnected-(DD3-PB7-Pad43)") (class "Default")
      (node (ref "DD3") (pin "43") (pinfunction "PB7_43") (pintype "passive"))
    )
    (net (code "56") (name "unconnected-(DD3-PB8-Pad45)") (class "Default")
      (node (ref "DD3") (pin "45") (pinfunction "PB8_45") (pintype "passive"))
    )
    (net (code "57") (name "unconnected-(DD3-PB9-Pad46)") (class "Default")
      (node (ref "DD3") (pin "46") (pinfunction "PB9_46") (pintype "passive"))
    )
    (net (code "58") (name "unconnected-(DD3-PB12-Pad25)") (class "Default")
      (node (ref "DD3") (pin "25") (pinfunction "PB12_25") (pintype "passive"))
    )
    (net (code "59") (name "unconnected-(DD3-PB13-Pad26)") (class "Default")
      (node (ref "DD3") (pin "26") (pinfunction "PB13_26") (pintype "passive"))
    )
    (net (code "60") (name "unconnected-(DD3-PB14-Pad27)") (class "Default")
      (node (ref "DD3") (pin "27") (pinfunction "PB14_27") (pintype "passive"))
    )
    (net (code "61") (name "unconnected-(DD3-PB15-Pad28)") (class "Default")
      (node (ref "DD3") (pin "28") (pinfunction "PB15_28") (pintype "passive"))
    )
    (net (code "62") (name "unconnected-(DD3-PC13{slash}TAMPER{slash}RTc-Pad2)") (class "Default")
      (node (ref "DD3") (pin "2") (pinfunction "PC13/TAMPER/RTc_2") (pintype "passive"))
    )
    (net (code "63") (name "unconnected-(DD3-PC14{slash}OSC32in-Pad3)") (class "Default")
      (node (ref "DD3") (pin "3") (pinfunction "PC14/OSC32in_3") (pintype "passive"))
    )
    (net (code "64") (name "unconnected-(DD3-PC15{slash}OSC32out-Pad4)") (class "Default")
      (node (ref "DD3") (pin "4") (pinfunction "PC15/OSC32out_4") (pintype "passive"))
    )
    (net (code "65") (name "unconnected-(DD3-SCL{slash}PB10-Pad21)") (class "Default")
      (node (ref "DD3") (pin "21") (pinfunction "SCL/PB10_21") (pintype "passive"))
    )
    (net (code "66") (name "unconnected-(DD3-SDA{slash}PB11-Pad22)") (class "Default")
      (node (ref "DD3") (pin "22") (pinfunction "SDA/PB11_22") (pintype "passive"))
    )
    (net (code "67") (name "unconnected-(DD3-TRACESWO{slash}PB3-Pad39)") (class "Default")
      (node (ref "DD3") (pin "39") (pinfunction "TRACESWO/PB3_39") (pintype "passive"))
    )
    (net (code "68") (name "unconnected-(DD3-VBAT-Pad1)") (class "Default")
      (node (ref "DD3") (pin "1") (pinfunction "VBAT_1") (pintype "passive"))
    )
    (net (code "69") (name "unconnected-(DD4-SHDN-Pad5)") (class "Default")
      (node (ref "DD4") (pin "5") (pinfunction "SHDN_5") (pintype "passive+no_connect"))
    )
  )
)
